# thruhole.net
KiCad netlist of a schematic drawn in EAGLE
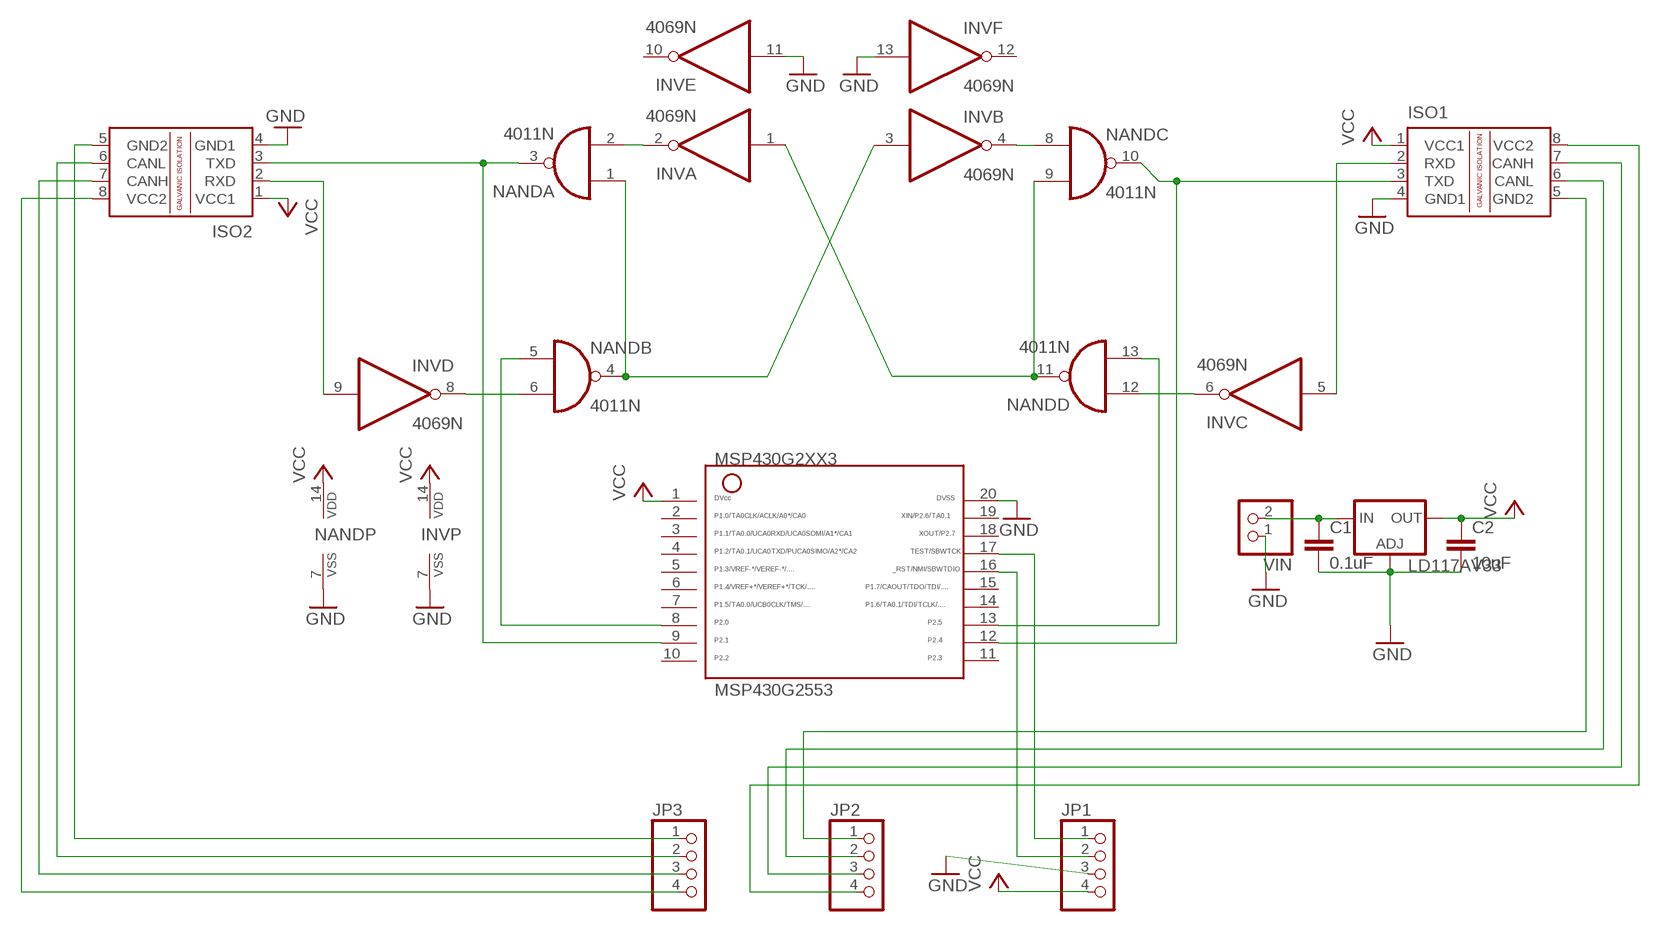
[diagram p0: schematic, sheet 1]

(export (version "E")
  (design (tool "Eeschema 10.0.6"))
  (components
    (comp (ref "C1")
      (value "0.1uF")
      (footprint "eagle-import:C025-024X044")
      (libsource (lib "eagle-import") (part "C-EU025-024X044"))
    )
    (comp (ref "C2")
      (value "10uF")
      (footprint "eagle-import:C025-024X044")
      (libsource (lib "eagle-import") (part "C-EU025-024X044"))
    )
    (comp (ref "INV")
      (value "4069N")
      (footprint "eagle-import:DIL14")
      (libsource (lib "eagle-import") (part "4069N"))
    )
    (comp (ref "ISO1")
      (value "ISO1050DUB")
      (footprint "eagle-import:DUB-R-PDSO-G8")
      (fields (field (name "MPN") "ISO1050DUBR"))
      (libsource (lib "eagle-import") (part "ISO1050DUB"))
    )
    (comp (ref "ISO2")
      (value "ISO1050DUB")
      (footprint "eagle-import:DUB-R-PDSO-G8")
      (fields (field (name "MPN") "ISO1050DUBR"))
      (libsource (lib "eagle-import") (part "ISO1050DUB"))
    )
    (comp (ref "JP1")
      (value "PINHD-1X4")
      (footprint "eagle-import:1X04")
      (libsource (lib "eagle-import") (part "PINHD-1X4"))
    )
    (comp (ref "JP2")
      (value "PINHD-1X4")
      (footprint "eagle-import:1X04")
      (libsource (lib "eagle-import") (part "PINHD-1X4"))
    )
    (comp (ref "JP3")
      (value "PINHD-1X4")
      (footprint "eagle-import:1X04")
      (libsource (lib "eagle-import") (part "PINHD-1X4"))
    )
    (comp (ref "LD117AV33")
      (value "LD117AV33")
      (footprint "eagle-import:TO220L1")
      (libsource (lib "eagle-import") (part "LD117A?V33"))
    )
    (comp (ref "MSP430G2553")
      (value "G2XX3---N20")
      (footprint "eagle-import:N20")
      (libsource (lib "eagle-import") (part "G2XX3---N20"))
    )
    (comp (ref "NAND")
      (value "4011N")
      (footprint "eagle-import:DIL14")
      (libsource (lib "eagle-import") (part "4011N"))
    )
    (comp (ref "VIN")
      (value "PINHD-1X2")
      (footprint "eagle-import:1X02")
      (libsource (lib "eagle-import") (part "PINHD-1X2"))
    )
  )
  (nets
    (net (code "1") (name "GND") (class "Default")
      (node (ref "C1") (pin "2") (pinfunction "2_2") (pintype "passive"))
      (node (ref "C2") (pin "2") (pinfunction "2_2") (pintype "passive"))
      (node (ref "INV") (pin "11") (pinfunction "I_11") (pintype "input"))
      (node (ref "INV") (pin "13") (pinfunction "I_13") (pintype "input"))
      (node (ref "INV") (pin "7") (pinfunction "VSS_7") (pintype "power_in"))
      (node (ref "ISO1") (pin "4") (pinfunction "GND1_4") (pintype "input"))
      (node (ref "ISO2") (pin "4") (pinfunction "GND1_4") (pintype "input"))
      (node (ref "JP1") (pin "3") (pinfunction "3_3") (pintype "passive"))
      (node (ref "LD117AV33") (pin "1") (pinfunction "ADJ_1") (pintype "input"))
      (node (ref "MSP430G2553") (pin "20") (pinfunction "20_20") (pintype "bidirectional"))
      (node (ref "NAND") (pin "7") (pinfunction "VSS_7") (pintype "power_in"))
      (node (ref "VIN") (pin "1") (pinfunction "1_1") (pintype "passive"))
    )
    (net (code "2") (name "Net-(INVA-I)") (class "Default")
      (node (ref "INV") (pin "1") (pinfunction "I_1") (pintype "input"))
      (node (ref "NAND") (pin "11") (pinfunction "O_11") (pintype "output"))
      (node (ref "NAND") (pin "9") (pinfunction "I1_9") (pintype "input"))
    )
    (net (code "3") (name "Net-(INVA-O)") (class "Default")
      (node (ref "INV") (pin "2") (pinfunction "O_2") (pintype "output"))
      (node (ref "NAND") (pin "2") (pinfunction "I1_2") (pintype "input"))
    )
    (net (code "4") (name "Net-(INVB-I)") (class "Default")
      (node (ref "INV") (pin "3") (pinfunction "I_3") (pintype "input"))
      (node (ref "NAND") (pin "1") (pinfunction "I0_1") (pintype "input"))
      (node (ref "NAND") (pin "4") (pinfunction "O_4") (pintype "output"))
    )
    (net (code "5") (name "Net-(INVB-O)") (class "Default")
      (node (ref "INV") (pin "4") (pinfunction "O_4") (pintype "output"))
      (node (ref "NAND") (pin "8") (pinfunction "I0_8") (pintype "input"))
    )
    (net (code "6") (name "Net-(INVC-I)") (class "Default")
      (node (ref "INV") (pin "5") (pinfunction "I_5") (pintype "input"))
      (node (ref "ISO1") (pin "2") (pinfunction "RXD_2") (pintype "input"))
    )
    (net (code "7") (name "Net-(INVC-O)") (class "Default")
      (node (ref "INV") (pin "6") (pinfunction "O_6") (pintype "output"))
      (node (ref "NAND") (pin "12") (pinfunction "I0_12") (pintype "input"))
    )
    (net (code "8") (name "Net-(INVD-I)") (class "Default")
      (node (ref "INV") (pin "9") (pinfunction "I_9") (pintype "input"))
      (node (ref "ISO2") (pin "2") (pinfunction "RXD_2") (pintype "input"))
    )
    (net (code "9") (name "Net-(INVD-O)") (class "Default")
      (node (ref "INV") (pin "8") (pinfunction "O_8") (pintype "output"))
      (node (ref "NAND") (pin "6") (pinfunction "I1_6") (pintype "input"))
    )
    (net (code "10") (name "Net-(ISO1-CANH)") (class "Default")
      (node (ref "ISO1") (pin "7") (pinfunction "CANH_7") (pintype "input"))
      (node (ref "JP2") (pin "3") (pinfunction "3_3") (pintype "passive"))
    )
    (net (code "11") (name "Net-(ISO1-CANL)") (class "Default")
      (node (ref "ISO1") (pin "6") (pinfunction "CANL_6") (pintype "input"))
      (node (ref "JP2") (pin "2") (pinfunction "2_2") (pintype "passive"))
    )
    (net (code "12") (name "Net-(ISO1-GND2)") (class "Default")
      (node (ref "ISO1") (pin "5") (pinfunction "GND2_5") (pintype "input"))
      (node (ref "JP2") (pin "1") (pinfunction "1_1") (pintype "passive"))
    )
    (net (code "13") (name "Net-(ISO1-TXD)") (class "Default")
      (node (ref "ISO1") (pin "3") (pinfunction "TXD_3") (pintype "input"))
      (node (ref "MSP430G2553") (pin "12") (pinfunction "12_12") (pintype "bidirectional"))
      (node (ref "NAND") (pin "10") (pinfunction "O_10") (pintype "output"))
    )
    (net (code "14") (name "Net-(ISO1-VCC2)") (class "Default")
      (node (ref "ISO1") (pin "8") (pinfunction "VCC2_8") (pintype "input"))
      (node (ref "JP2") (pin "4") (pinfunction "4_4") (pintype "passive"))
    )
    (net (code "15") (name "Net-(ISO2-CANH)") (class "Default")
      (node (ref "ISO2") (pin "7") (pinfunction "CANH_7") (pintype "input"))
      (node (ref "JP3") (pin "3") (pinfunction "3_3") (pintype "passive"))
    )
    (net (code "16") (name "Net-(ISO2-CANL)") (class "Default")
      (node (ref "ISO2") (pin "6") (pinfunction "CANL_6") (pintype "input"))
      (node (ref "JP3") (pin "2") (pinfunction "2_2") (pintype "passive"))
    )
    (net (code "17") (name "Net-(ISO2-GND2)") (class "Default")
      (node (ref "ISO2") (pin "5") (pinfunction "GND2_5") (pintype "input"))
      (node (ref "JP3") (pin "1") (pinfunction "1_1") (pintype "passive"))
    )
    (net (code "18") (name "Net-(ISO2-TXD)") (class "Default")
      (node (ref "ISO2") (pin "3") (pinfunction "TXD_3") (pintype "input"))
      (node (ref "MSP430G2553") (pin "9") (pinfunction "9_9") (pintype "bidirectional"))
      (node (ref "NAND") (pin "3") (pinfunction "O_3") (pintype "output"))
    )
    (net (code "19") (name "Net-(ISO2-VCC2)") (class "Default")
      (node (ref "ISO2") (pin "8") (pinfunction "VCC2_8") (pintype "input"))
      (node (ref "JP3") (pin "4") (pinfunction "4_4") (pintype "passive"))
    )
    (net (code "20") (name "Net-(JP1-Pad1)") (class "Default")
      (node (ref "JP1") (pin "1") (pinfunction "1_1") (pintype "passive"))
      (node (ref "MSP430G2553") (pin "17") (pinfunction "17_17") (pintype "bidirectional"))
    )
    (net (code "21") (name "Net-(JP1-Pad2)") (class "Default")
      (node (ref "JP1") (pin "2") (pinfunction "2_2") (pintype "passive"))
      (node (ref "MSP430G2553") (pin "16") (pinfunction "16_16") (pintype "bidirectional"))
    )
    (net (code "22") (name "Net-(LD117AV33-IN)") (class "Default")
      (node (ref "C1") (pin "1") (pinfunction "1_1") (pintype "passive"))
      (node (ref "LD117AV33") (pin "3") (pinfunction "IN_3") (pintype "input"))
      (node (ref "VIN") (pin "2") (pinfunction "2_2") (pintype "passive"))
    )
    (net (code "23") (name "Net-(NANDB-I0)") (class "Default")
      (node (ref "MSP430G2553") (pin "8") (pinfunction "8_8") (pintype "bidirectional"))
      (node (ref "NAND") (pin "5") (pinfunction "I0_5") (pintype "input"))
    )
    (net (code "24") (name "Net-(NANDD-I1)") (class "Default")
      (node (ref "MSP430G2553") (pin "13") (pinfunction "13_13") (pintype "bidirectional"))
      (node (ref "NAND") (pin "13") (pinfunction "I1_13") (pintype "input"))
    )
    (net (code "25") (name "VCC") (class "Default")
      (node (ref "C2") (pin "1") (pinfunction "1_1") (pintype "passive"))
      (node (ref "INV") (pin "14") (pinfunction "VDD_14") (pintype "power_in"))
      (node (ref "ISO1") (pin "1") (pinfunction "VCC1_1") (pintype "input"))
      (node (ref "ISO2") (pin "1") (pinfunction "VCC1_1") (pintype "input"))
      (node (ref "JP1") (pin "4") (pinfunction "4_4") (pintype "passive"))
      (node (ref "LD117AV33") (pin "2") (pinfunction "OUT_2") (pintype "passive"))
      (node (ref "MSP430G2553") (pin "1") (pinfunction "1_1") (pintype "bidirectional"))
      (node (ref "NAND") (pin "14") (pinfunction "VDD_14") (pintype "power_in"))
    )
    (net (code "26") (name "unconnected-(INVE-O-Pad10)") (class "Default")
      (node (ref "INV") (pin "10") (pinfunction "O_10") (pintype "output"))
    )
    (net (code "27") (name "unconnected-(INVF-O-Pad12)") (class "Default")
      (node (ref "INV") (pin "12") (pinfunction "O_12") (pintype "output"))
    )
    (net (code "28") (name "unconnected-(MSP430G2553-Pad2)") (class "Default")
      (node (ref "MSP430G2553") (pin "2") (pinfunction "2_2") (pintype "bidirectional"))
    )
    (net (code "29") (name "unconnected-(MSP430G2553-Pad3)") (class "Default")
      (node (ref "MSP430G2553") (pin "3") (pinfunction "3_3") (pintype "bidirectional"))
    )
    (net (code "30") (name "unconnected-(MSP430G2553-Pad4)") (class "Default")
      (node (ref "MSP430G2553") (pin "4") (pinfunction "4_4") (pintype "bidirectional"))
    )
    (net (code "31") (name "unconnected-(MSP430G2553-Pad5)") (class "Default")
      (node (ref "MSP430G2553") (pin "5") (pinfunction "5_5") (pintype "bidirectional"))
    )
    (net (code "32") (name "unconnected-(MSP430G2553-Pad6)") (class "Default")
      (node (ref "MSP430G2553") (pin "6") (pinfunction "6_6") (pintype "bidirectional"))
    )
    (net (code "33") (name "unconnected-(MSP430G2553-Pad7)") (class "Default")
      (node (ref "MSP430G2553") (pin "7") (pinfunction "7_7") (pintype "bidirectional"))
    )
    (net (code "34") (name "unconnected-(MSP430G2553-Pad10)") (class "Default")
      (node (ref "MSP430G2553") (pin "10") (pinfunction "10_10") (pintype "bidirectional"))
    )
    (net (code "35") (name "unconnected-(MSP430G2553-Pad11)") (class "Default")
      (node (ref "MSP430G2553") (pin "11") (pinfunction "11_11") (pintype "bidirectional"))
    )
    (net (code "36") (name "unconnected-(MSP430G2553-Pad14)") (class "Default")
      (node (ref "MSP430G2553") (pin "14") (pinfunction "14_14") (pintype "bidirectional"))
    )
    (net (code "37") (name "unconnected-(MSP430G2553-Pad15)") (class "Default")
      (node (ref "MSP430G2553") (pin "15") (pinfunction "15_15") (pintype "bidirectional"))
    )
    (net (code "38") (name "unconnected-(MSP430G2553-Pad18)") (class "Default")
      (node (ref "MSP430G2553") (pin "18") (pinfunction "18_18") (pintype "bidirectional"))
    )
    (net (code "39") (name "unconnected-(MSP430G2553-Pad19)") (class "Default")
      (node (ref "MSP430G2553") (pin "19") (pinfunction "19_19") (pintype "bidirectional"))
    )
  )
)
